# multiSheet1.net
KiCad netlist of a schematic drawn in Altium Designer
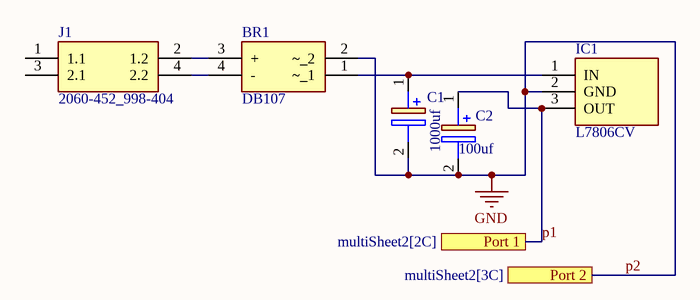
[diagram p0: multiSheet1.SchDoc]

(export (version "E")
  (design (tool "Eeschema 10.0.6"))
  (components
    (comp (ref "BR1")
      (value "DB107")
      (footprint "SamacSys:DIP825W50P510L830H340Q4N")
      (description "Bridge Rectifier")
      (fields (field (name "MOUSER PART NUMBER") "583-DB107"))
      (libsource (lib "*") (part "DB107"))
    )
    (comp (ref "C1")
      (value "1000uf")
      (footprint "SamacSys:CAPPRD550W60D1050H2150")
      (description "Capacitor Polarised")
      (fields (field (name "MANUFACTURER_PART_NUMBER") "108CKE025M"))
      (libsource (lib "*") (part "108CKE025M"))
    )
    (comp (ref "C2")
      (value "100uf")
      (footprint "SamacSys:CAPPRD500W65D1000H3200")
      (description "Capacitor Polarised")
      (fields
        (field (name "MANUFACTURER_PART_NUMBER") "EEU-FC2A101L")
        (field (name "MOUSER PART NUMBER") "667-EEU-FC2A101L")
      )
      (libsource (lib "*") (part "EEU-FC2A101L"))
    )
    (comp (ref "IC1")
      (value "L7806CV")
      (footprint "SamacSys:TO270P460X1020X2008-3P")
      (description "Integrated Circuit")
      (fields (field (name "MOUSER PART NUMBER") "511-L7806CV"))
      (libsource (lib "*") (part "L7806CV"))
    )
    (comp (ref "J1")
      (value "2060-452_998-404")
      (footprint "SamacSys:2060452998404")
      (description "Connector")
      (fields (field (name "MANUFACTURER_PART_NUMBER") "2060-452/998-404"))
      (libsource (lib "*") (part "2060-452_998-404"))
    )
  )
  (nets
    (net (code "1") (name "/p1") (class "Default")
      (node (ref "C2") (pin "1") (pinfunction "+_1") (pintype "passive"))
      (node (ref "IC1") (pin "3") (pinfunction "OUT_3") (pintype "power_in"))
    )
    (net (code "2") (name "GND") (class "Default")
      (node (ref "BR1") (pin "2") (pinfunction "~_2_2") (pintype "passive"))
      (node (ref "C1") (pin "2") (pinfunction "-_2") (pintype "passive"))
      (node (ref "C2") (pin "2") (pinfunction "-_2") (pintype "passive"))
      (node (ref "IC1") (pin "2") (pinfunction "GND_2") (pintype "power_in"))
    )
    (net (code "3") (name "Net-(BR1-+)") (class "Default")
      (node (ref "BR1") (pin "3") (pinfunction "+_3") (pintype "passive"))
      (node (ref "J1") (pin "2") (pinfunction "1.2_2") (pintype "passive"))
    )
    (net (code "4") (name "Net-(BR1--)") (class "Default")
      (node (ref "BR1") (pin "4") (pinfunction "-_4") (pintype "passive"))
      (node (ref "J1") (pin "4") (pinfunction "2.2_4") (pintype "passive"))
    )
    (net (code "5") (name "Net-(BR1-~_1)") (class "Default")
      (node (ref "BR1") (pin "1") (pinfunction "~_1_1") (pintype "passive"))
      (node (ref "C1") (pin "1") (pinfunction "+_1") (pintype "passive"))
      (node (ref "IC1") (pin "1") (pinfunction "IN_1") (pintype "power_in"))
    )
    (net (code "6") (name "unconnected-(J1-1.1-Pad1)") (class "Default")
      (node (ref "J1") (pin "1") (pinfunction "1.1_1") (pintype "passive"))
    )
    (net (code "7") (name "unconnected-(J1-2.1-Pad3)") (class "Default")
      (node (ref "J1") (pin "3") (pinfunction "2.1_3") (pintype "passive"))
    )
  )
)
